# roach-fem.net
KiCad netlist of a schematic drawn in EAGLE
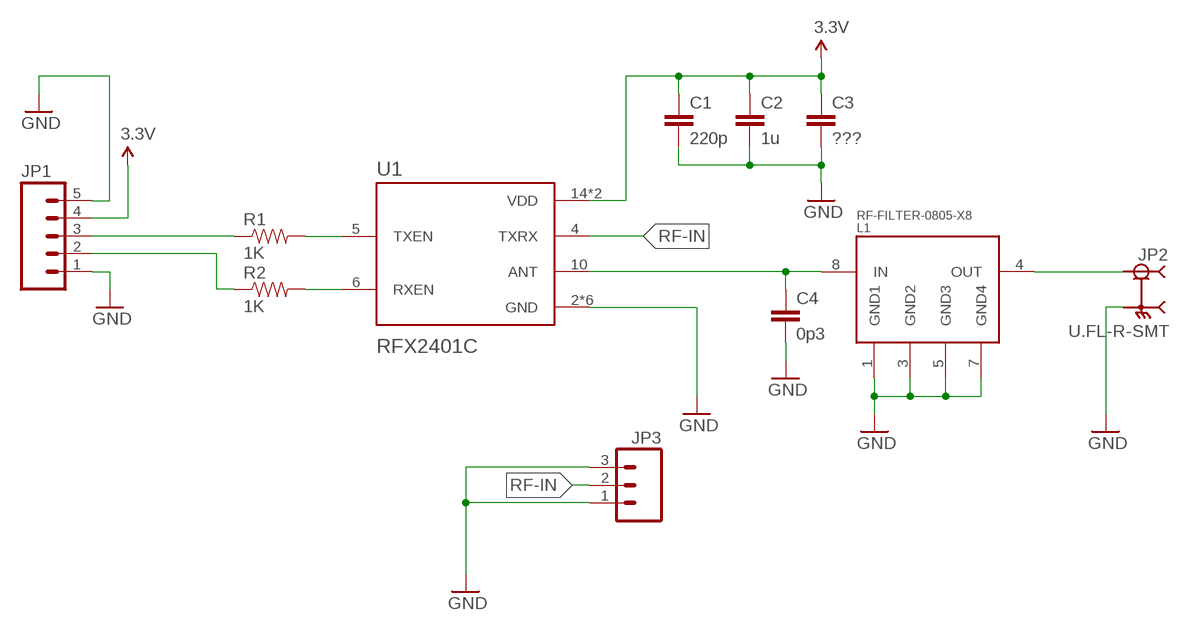
[diagram p0: schematic, sheet 1]

(export (version "E")
  (design (tool "Eeschema 10.0.6"))
  (components
    (comp (ref "C1")
      (value "220p")
      (footprint "eagle-import:0603-CAP")
      (libsource (lib "eagle-import") (part "CAP0603-CAP"))
    )
    (comp (ref "C2")
      (value "1u")
      (footprint "eagle-import:0603-CAP")
      (libsource (lib "eagle-import") (part "CAP0603-CAP"))
    )
    (comp (ref "C3")
      (value "???")
      (footprint "eagle-import:0603-CAP")
      (libsource (lib "eagle-import") (part "CAP0603-CAP"))
    )
    (comp (ref "C4")
      (value "0p3")
      (footprint "eagle-import:0402-CAP")
      (libsource (lib "eagle-import") (part "CAP0402-CAP"))
    )
    (comp (ref "JP1")
      (value "M05PTH")
      (footprint "eagle-import:1X05")
      (libsource (lib "eagle-import") (part "M05PTH"))
    )
    (comp (ref "JP2")
      (value "U.FL-R-SMT")
      (footprint "eagle-import:HRS_U.FL-R-SMT(10)")
      (fields (field (name "MF") "Hirose Electric Co Ltd") (field (name "MP") "U.FL-R-SMT(10)"))
      (libsource (lib "eagle-import") (part "U.FL-R-SMT(10)"))
    )
    (comp (ref "JP3")
      (value "M03PTH")
      (footprint "eagle-import:1X03")
      (libsource (lib "eagle-import") (part "M03PTH"))
    )
    (comp (ref "L1")
      (value "RF-FILTER-0805-X8")
      (footprint "eagle-import:RF-FILTER-0805")
      (libsource (lib "eagle-import") (part "RF-FILTER-0805-X8"))
    )
    (comp (ref "R1")
      (value "1K")
      (footprint "eagle-import:0603-RES")
      (libsource (lib "eagle-import") (part "RESISTOR0603-RES"))
    )
    (comp (ref "R2")
      (value "1K")
      (footprint "eagle-import:0603-RES")
      (libsource (lib "eagle-import") (part "RESISTOR0603-RES"))
    )
    (comp (ref "U1")
      (value "RFX2401C")
      (footprint "eagle-import:QFN50P300X300X60-17N")
      (fields (field (name "MF") "Skyworks Solutions"))
      (libsource (lib "eagle-import") (part "RFX2401C"))
    )
  )
  (nets
    (net (code "1") (name "3.3V") (class "Default")
      (node (ref "C1") (pin "1") (pinfunction "1_1") (pintype "passive"))
      (node (ref "C2") (pin "1") (pinfunction "1_1") (pintype "passive"))
      (node (ref "C3") (pin "1") (pinfunction "1_1") (pintype "passive"))
      (node (ref "JP1") (pin "4") (pinfunction "4_4") (pintype "passive"))
      (node (ref "U1") (pin "14") (pinfunction "VDD_14") (pintype "power_in"))
      (node (ref "U1") (pin "16") (pinfunction "VDD_16") (pintype "power_in"))
    )
    (net (code "2") (name "GND") (class "Default")
      (node (ref "C1") (pin "2") (pinfunction "2_2") (pintype "passive"))
      (node (ref "C2") (pin "2") (pinfunction "2_2") (pintype "passive"))
      (node (ref "C3") (pin "2") (pinfunction "2_2") (pintype "passive"))
      (node (ref "C4") (pin "2") (pinfunction "2_2") (pintype "passive"))
      (node (ref "JP1") (pin "1") (pinfunction "1_1") (pintype "passive"))
      (node (ref "JP1") (pin "5") (pinfunction "5_5") (pintype "passive"))
      (node (ref "JP2") (pin "2") (pinfunction "GND_2") (pintype "passive"))
      (node (ref "JP2") (pin "3") (pinfunction "GND_3") (pintype "passive"))
      (node (ref "JP3") (pin "1") (pinfunction "1_1") (pintype "passive"))
      (node (ref "JP3") (pin "3") (pinfunction "3_3") (pintype "passive"))
      (node (ref "L1") (pin "1") (pinfunction "GND1_1") (pintype "bidirectional"))
      (node (ref "L1") (pin "3") (pinfunction "GND2_3") (pintype "bidirectional"))
      (node (ref "L1") (pin "5") (pinfunction "GND3_5") (pintype "bidirectional"))
      (node (ref "L1") (pin "7") (pinfunction "GND4_7") (pintype "bidirectional"))
      (node (ref "U1") (pin "11") (pinfunction "GND_11") (pintype "power_in"))
      (node (ref "U1") (pin "17") (pinfunction "GND_17") (pintype "power_in"))
      (node (ref "U1") (pin "2") (pinfunction "GND_2") (pintype "power_in"))
      (node (ref "U1") (pin "3") (pinfunction "GND_3") (pintype "power_in"))
      (node (ref "U1") (pin "8") (pinfunction "GND_8") (pintype "power_in"))
      (node (ref "U1") (pin "9") (pinfunction "GND_9") (pintype "power_in"))
    )
    (net (code "3") (name "Net-(JP1-Pad2)") (class "Default")
      (node (ref "JP1") (pin "2") (pinfunction "2_2") (pintype "passive"))
      (node (ref "R2") (pin "1") (pinfunction "1_1") (pintype "passive"))
    )
    (net (code "4") (name "Net-(JP1-Pad3)") (class "Default")
      (node (ref "JP1") (pin "3") (pinfunction "3_3") (pintype "passive"))
      (node (ref "R1") (pin "1") (pinfunction "1_1") (pintype "passive"))
    )
    (net (code "5") (name "Net-(JP2-SIG)") (class "Default")
      (node (ref "JP2") (pin "1") (pinfunction "SIG_1") (pintype "passive"))
      (node (ref "L1") (pin "4") (pinfunction "OUT_4") (pintype "bidirectional"))
    )
    (net (code "6") (name "Net-(L1-IN)") (class "Default")
      (node (ref "C4") (pin "1") (pinfunction "1_1") (pintype "passive"))
      (node (ref "L1") (pin "8") (pinfunction "IN_8") (pintype "bidirectional"))
      (node (ref "U1") (pin "10") (pinfunction "ANT_10") (pintype "passive"))
    )
    (net (code "7") (name "Net-(U1-RXEN)") (class "Default")
      (node (ref "R2") (pin "2") (pinfunction "2_2") (pintype "passive"))
      (node (ref "U1") (pin "6") (pinfunction "RXEN_6") (pintype "input"))
    )
    (net (code "8") (name "Net-(U1-TXEN)") (class "Default")
      (node (ref "R1") (pin "2") (pinfunction "2_2") (pintype "passive"))
      (node (ref "U1") (pin "5") (pinfunction "TXEN_5") (pintype "input"))
    )
    (net (code "9") (name "RF-IN") (class "Default")
      (node (ref "JP3") (pin "2") (pinfunction "2_2") (pintype "passive"))
      (node (ref "U1") (pin "4") (pinfunction "TXRX_4") (pintype "bidirectional"))
    )
  )
)
